# 03-MCU.net
KiCad netlist of a schematic drawn in Altium Designer
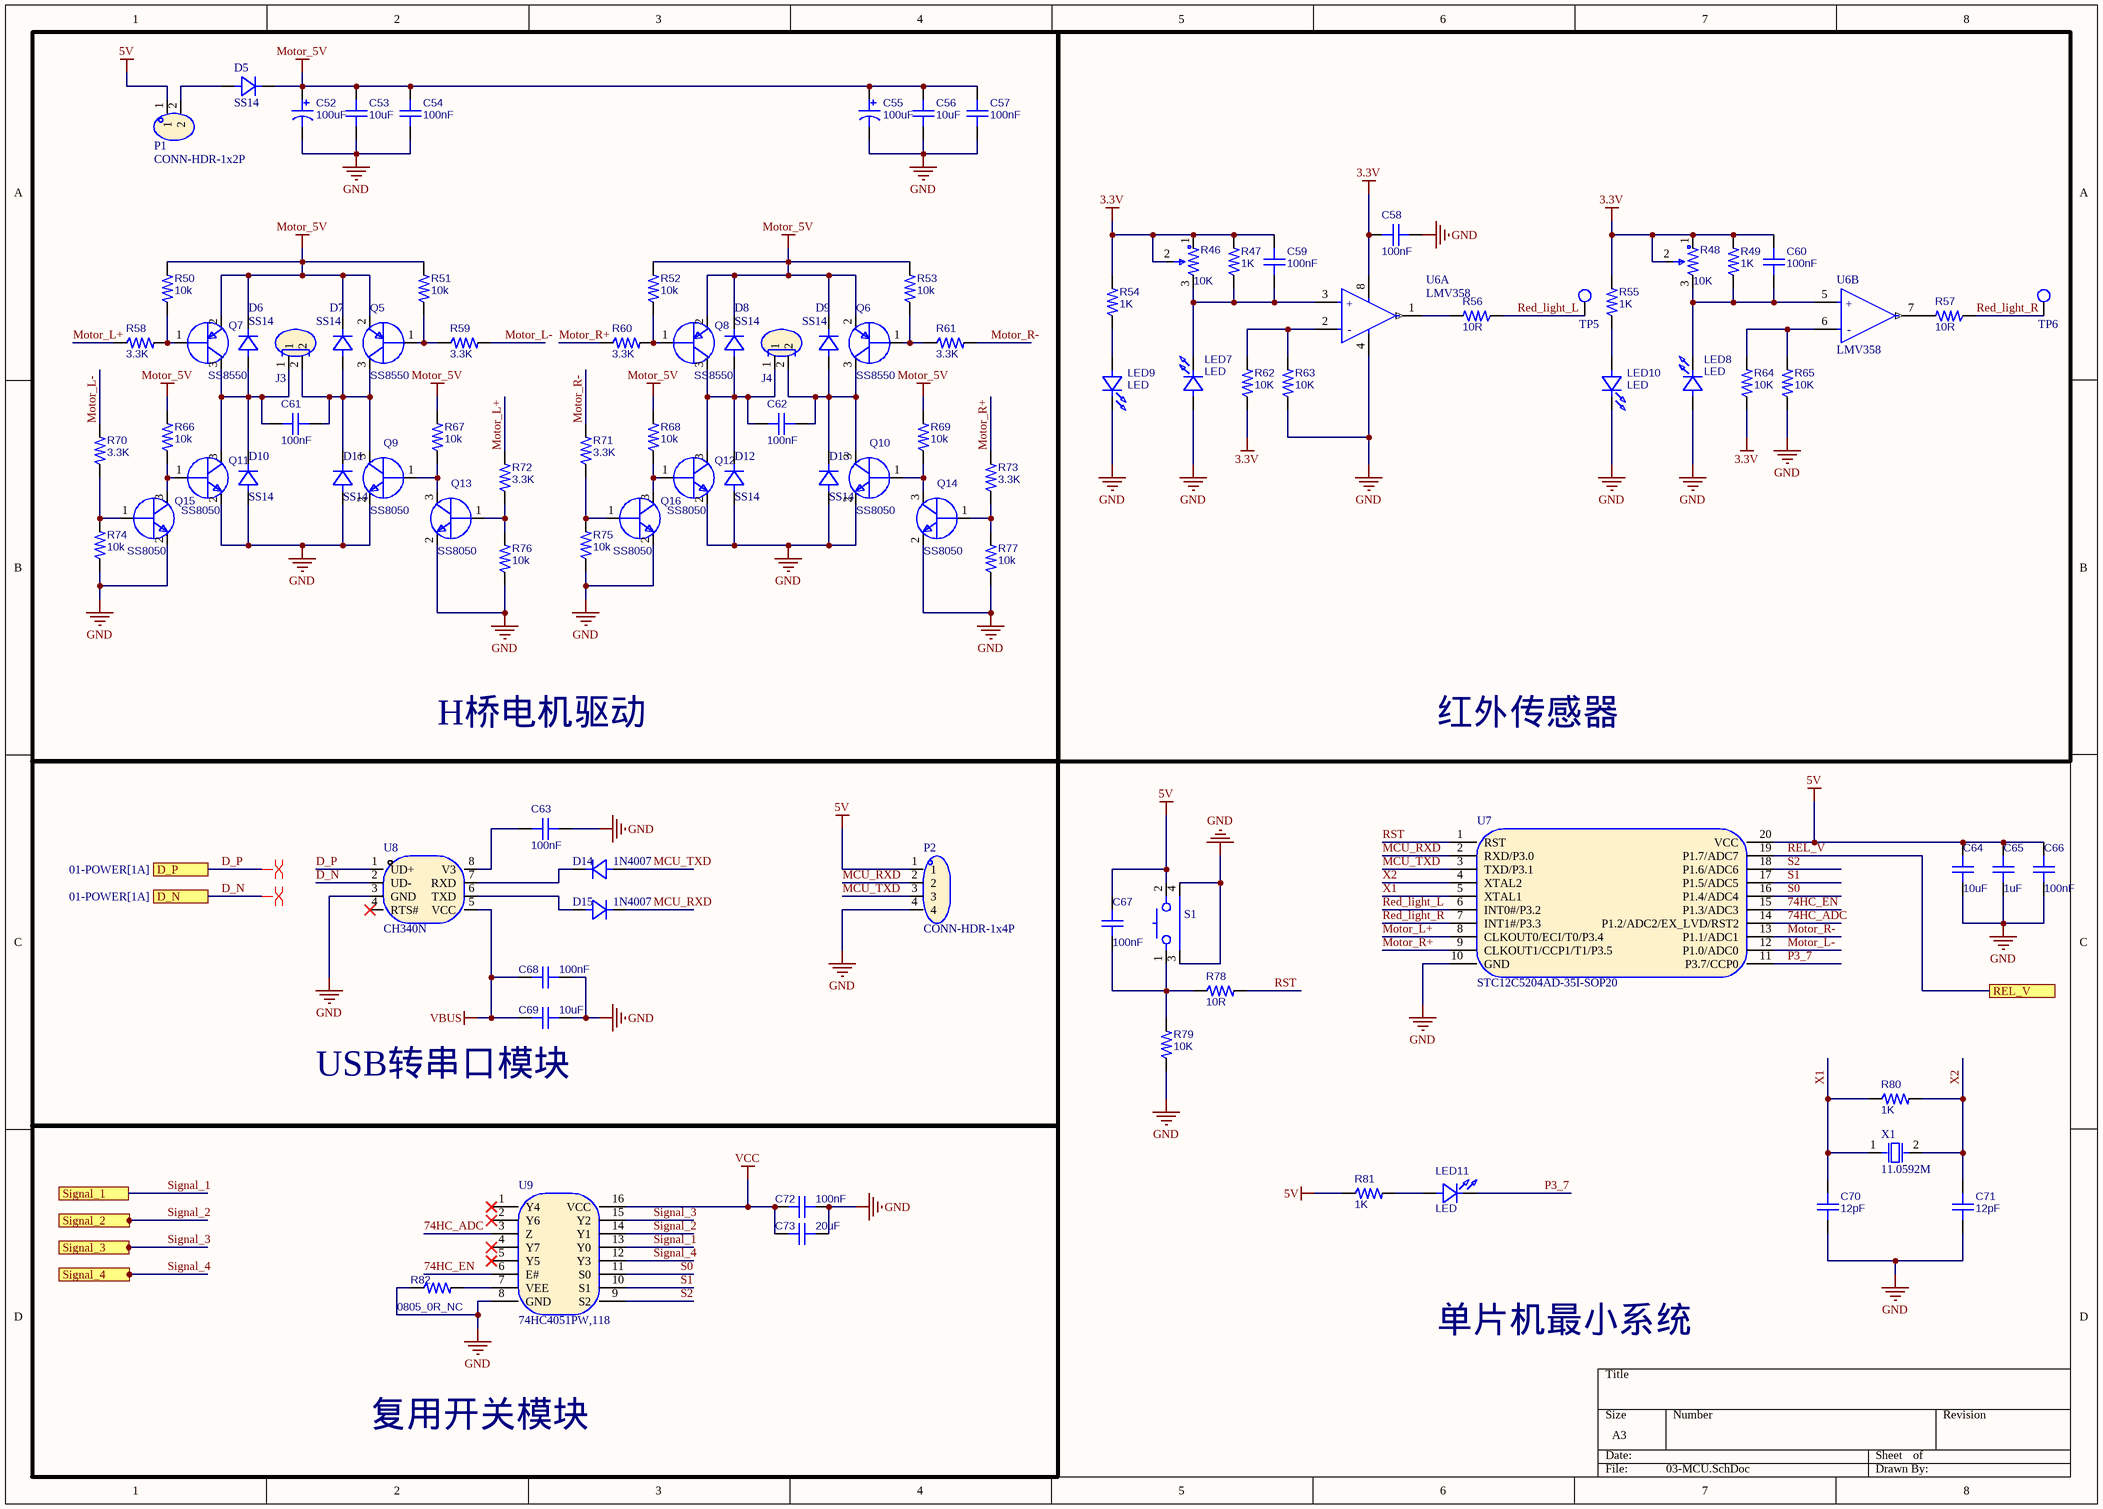
[diagram p0: 03-MCU.SchDoc]

(export (version "E")
  (design (tool "Eeschema 10.0.6"))
  (components
    (comp (ref "C52")
      (value "100uF")
      (footprint "CAPA-TH-5020-P2.0")
      (description "电解电容")
      (fields
        (field (name "BOM_MANUFACTURER PART") "普通黑色470UF 50V")
        (field (name "BOM_SUPPLIER PART") "C34642")
      )
      (libsource (lib "声源跟踪小车原理图库") (part "CAPA"))
    )
    (comp (ref "C53")
      (value "10uF")
      (footprint "CAP-SMD-0603")
      (description "贴片电容")
      (fields
        (field (name "BOM_MANUFACTURER PART") "CL03A104KQ3NNNC")
        (field (name "BOM_SUPPLIER PART") "C160831")
        (field (name "CONTRIBUTOR") "LCSC")
      )
      (libsource (lib "声源跟踪小车原理图库") (part "CAP"))
    )
    (comp (ref "C54")
      (value "100nF")
      (footprint "CAP-SMD-0603")
      (description "贴片电容")
      (fields
        (field (name "BOM_MANUFACTURER PART") "CL03A104KQ3NNNC")
        (field (name "BOM_SUPPLIER PART") "C160831")
        (field (name "CONTRIBUTOR") "LCSC")
      )
      (libsource (lib "声源跟踪小车原理图库") (part "CAP"))
    )
    (comp (ref "C55")
      (value "100uF")
      (footprint "CAPA-TH-5020-P2.0")
      (description "电解电容")
      (fields
        (field (name "BOM_MANUFACTURER PART") "普通黑色470UF 50V")
        (field (name "BOM_SUPPLIER PART") "C34642")
      )
      (libsource (lib "声源跟踪小车原理图库") (part "CAPA"))
    )
    (comp (ref "C56")
      (value "10uF")
      (footprint "CAP-SMD-0603")
      (description "贴片电容")
      (fields
        (field (name "BOM_MANUFACTURER PART") "CL03A104KQ3NNNC")
        (field (name "BOM_SUPPLIER PART") "C160831")
        (field (name "CONTRIBUTOR") "LCSC")
      )
      (libsource (lib "声源跟踪小车原理图库") (part "CAP"))
    )
    (comp (ref "C57")
      (value "100nF")
      (footprint "CAP-SMD-0603")
      (description "贴片电容")
      (fields
        (field (name "BOM_MANUFACTURER PART") "CL03A104KQ3NNNC")
        (field (name "BOM_SUPPLIER PART") "C160831")
        (field (name "CONTRIBUTOR") "LCSC")
      )
      (libsource (lib "声源跟踪小车原理图库") (part "CAP"))
    )
    (comp (ref "C58")
      (value "100nF")
      (footprint "CAP-SMD-0603")
      (description "贴片电容")
      (fields
        (field (name "BOM_MANUFACTURER PART") "CL03A104KQ3NNNC")
        (field (name "BOM_SUPPLIER PART") "C160831")
        (field (name "CONTRIBUTOR") "LCSC")
      )
      (libsource (lib "声源跟踪小车原理图库") (part "CAP"))
    )
    (comp (ref "C59")
      (value "100nF")
      (footprint "CAP-SMD-0603")
      (description "贴片电容")
      (fields
        (field (name "BOM_MANUFACTURER PART") "CL03A104KQ3NNNC")
        (field (name "BOM_SUPPLIER PART") "C160831")
        (field (name "CONTRIBUTOR") "LCSC")
      )
      (libsource (lib "声源跟踪小车原理图库") (part "CAP"))
    )
    (comp (ref "C60")
      (value "100nF")
      (footprint "CAP-SMD-0603")
      (description "贴片电容")
      (fields
        (field (name "BOM_MANUFACTURER PART") "CL03A104KQ3NNNC")
        (field (name "BOM_SUPPLIER PART") "C160831")
        (field (name "CONTRIBUTOR") "LCSC")
      )
      (libsource (lib "声源跟踪小车原理图库") (part "CAP"))
    )
    (comp (ref "C61")
      (value "100nF")
      (footprint "CAP-SMD-0603")
      (description "贴片电容")
      (fields
        (field (name "BOM_MANUFACTURER PART") "CL03A104KQ3NNNC")
        (field (name "BOM_SUPPLIER PART") "C160831")
        (field (name "CONTRIBUTOR") "LCSC")
      )
      (libsource (lib "声源跟踪小车原理图库") (part "CAP"))
    )
    (comp (ref "C62")
      (value "100nF")
      (footprint "CAP-SMD-0603")
      (description "贴片电容")
      (fields
        (field (name "BOM_MANUFACTURER PART") "CL03A104KQ3NNNC")
        (field (name "BOM_SUPPLIER PART") "C160831")
        (field (name "CONTRIBUTOR") "LCSC")
      )
      (libsource (lib "声源跟踪小车原理图库") (part "CAP"))
    )
    (comp (ref "C63")
      (value "100nF")
      (footprint "CAP-SMD-0603")
      (description "贴片电容")
      (fields
        (field (name "BOM_MANUFACTURER PART") "CL03A104KQ3NNNC")
        (field (name "BOM_SUPPLIER PART") "C160831")
        (field (name "CONTRIBUTOR") "LCSC")
      )
      (libsource (lib "声源跟踪小车原理图库") (part "CAP"))
    )
    (comp (ref "C64")
      (value "10uF")
      (footprint "CAP-SMD-0603")
      (description "贴片电容")
      (fields
        (field (name "BOM_MANUFACTURER PART") "CL03A104KQ3NNNC")
        (field (name "BOM_SUPPLIER PART") "C160831")
        (field (name "CONTRIBUTOR") "LCSC")
      )
      (libsource (lib "声源跟踪小车原理图库") (part "CAP"))
    )
    (comp (ref "C65")
      (value "1uF")
      (footprint "CAP-SMD-0603")
      (description "贴片电容")
      (fields
        (field (name "BOM_MANUFACTURER PART") "CL03A104KQ3NNNC")
        (field (name "BOM_SUPPLIER PART") "C160831")
        (field (name "CONTRIBUTOR") "LCSC")
      )
      (libsource (lib "声源跟踪小车原理图库") (part "CAP"))
    )
    (comp (ref "C66")
      (value "100nF")
      (footprint "CAP-SMD-0603")
      (description "贴片电容")
      (fields
        (field (name "BOM_MANUFACTURER PART") "CL03A104KQ3NNNC")
        (field (name "BOM_SUPPLIER PART") "C160831")
        (field (name "CONTRIBUTOR") "LCSC")
      )
      (libsource (lib "声源跟踪小车原理图库") (part "CAP"))
    )
    (comp (ref "C67")
      (value "100nF")
      (footprint "CAP-SMD-0603")
      (description "贴片电容")
      (fields
        (field (name "BOM_MANUFACTURER PART") "CL03A104KQ3NNNC")
        (field (name "BOM_SUPPLIER PART") "C160831")
        (field (name "CONTRIBUTOR") "LCSC")
      )
      (libsource (lib "声源跟踪小车原理图库") (part "CAP"))
    )
    (comp (ref "C68")
      (value "100nF")
      (footprint "CAP-SMD-0603")
      (description "贴片电容")
      (fields
        (field (name "BOM_MANUFACTURER PART") "CL03A104KQ3NNNC")
        (field (name "BOM_SUPPLIER PART") "C160831")
        (field (name "CONTRIBUTOR") "LCSC")
      )
      (libsource (lib "声源跟踪小车原理图库") (part "CAP"))
    )
    (comp (ref "C69")
      (value "10uF")
      (footprint "CAP-SMD-0603")
      (description "贴片电容")
      (fields
        (field (name "BOM_MANUFACTURER PART") "CL03A104KQ3NNNC")
        (field (name "BOM_SUPPLIER PART") "C160831")
        (field (name "CONTRIBUTOR") "LCSC")
      )
      (libsource (lib "声源跟踪小车原理图库") (part "CAP"))
    )
    (comp (ref "C70")
      (value "12pF")
      (footprint "CAP-SMD-0603")
      (description "贴片电容")
      (fields
        (field (name "BOM_MANUFACTURER PART") "CL03A104KQ3NNNC")
        (field (name "BOM_SUPPLIER PART") "C160831")
        (field (name "CONTRIBUTOR") "LCSC")
      )
      (libsource (lib "声源跟踪小车原理图库") (part "CAP"))
    )
    (comp (ref "C71")
      (value "12pF")
      (footprint "CAP-SMD-0603")
      (description "贴片电容")
      (fields
        (field (name "BOM_MANUFACTURER PART") "CL03A104KQ3NNNC")
        (field (name "BOM_SUPPLIER PART") "C160831")
        (field (name "CONTRIBUTOR") "LCSC")
      )
      (libsource (lib "声源跟踪小车原理图库") (part "CAP"))
    )
    (comp (ref "C72")
      (value "100nF")
      (footprint "CAP-SMD-0603")
      (description "贴片电容")
      (fields
        (field (name "BOM_MANUFACTURER PART") "CL03A104KQ3NNNC")
        (field (name "BOM_SUPPLIER PART") "C160831")
        (field (name "CONTRIBUTOR") "LCSC")
      )
      (libsource (lib "声源跟踪小车原理图库") (part "CAP"))
    )
    (comp (ref "C73")
      (value "20uF")
      (footprint "CAP-SMD-0603")
      (description "贴片电容")
      (fields
        (field (name "BOM_MANUFACTURER PART") "CL03A104KQ3NNNC")
        (field (name "BOM_SUPPLIER PART") "C160831")
        (field (name "CONTRIBUTOR") "LCSC")
      )
      (libsource (lib "声源跟踪小车原理图库") (part "CAP"))
    )
    (comp (ref "D5")
      (value "SS14")
      (footprint "SOD-123-P3.4")
      (description "二极管1N4148W")
      (fields (field (name "MANUFACTURER") "PSI(宝力芯)") (field (name "MANUFACTURER PART") "1N4148W"))
      (libsource (lib "声源跟踪小车原理图库") (part "Diode"))
    )
    (comp (ref "D6")
      (value "SS14")
      (footprint "SOD-123-P3.4")
      (description "二极管1N4148W")
      (fields (field (name "MANUFACTURER") "PSI(宝力芯)") (field (name "MANUFACTURER PART") "1N4148W"))
      (libsource (lib "声源跟踪小车原理图库") (part "Diode"))
    )
    (comp (ref "D7")
      (value "SS14")
      (footprint "SOD-123-P3.4")
      (description "二极管1N4148W")
      (fields (field (name "MANUFACTURER") "PSI(宝力芯)") (field (name "MANUFACTURER PART") "1N4148W"))
      (libsource (lib "声源跟踪小车原理图库") (part "Diode"))
    )
    (comp (ref "D8")
      (value "SS14")
      (footprint "SOD-123-P3.4")
      (description "二极管1N4148W")
      (fields (field (name "MANUFACTURER") "PSI(宝力芯)") (field (name "MANUFACTURER PART") "1N4148W"))
      (libsource (lib "声源跟踪小车原理图库") (part "Diode"))
    )
    (comp (ref "D9")
      (value "SS14")
      (footprint "SOD-123-P3.4")
      (description "二极管1N4148W")
      (fields (field (name "MANUFACTURER") "PSI(宝力芯)") (field (name "MANUFACTURER PART") "1N4148W"))
      (libsource (lib "声源跟踪小车原理图库") (part "Diode"))
    )
    (comp (ref "D10")
      (value "SS14")
      (footprint "SOD-123-P3.4")
      (description "二极管1N4148W")
      (fields (field (name "MANUFACTURER") "PSI(宝力芯)") (field (name "MANUFACTURER PART") "1N4148W"))
      (libsource (lib "声源跟踪小车原理图库") (part "Diode"))
    )
    (comp (ref "D11")
      (value "SS14")
      (footprint "SOD-123-P3.4")
      (description "二极管1N4148W")
      (fields (field (name "MANUFACTURER") "PSI(宝力芯)") (field (name "MANUFACTURER PART") "1N4148W"))
      (libsource (lib "声源跟踪小车原理图库") (part "Diode"))
    )
    (comp (ref "D12")
      (value "SS14")
      (footprint "SOD-123-P3.4")
      (description "二极管1N4148W")
      (fields (field (name "MANUFACTURER") "PSI(宝力芯)") (field (name "MANUFACTURER PART") "1N4148W"))
      (libsource (lib "声源跟踪小车原理图库") (part "Diode"))
    )
    (comp (ref "D13")
      (value "SS14")
      (footprint "SOD-123-P3.4")
      (description "二极管1N4148W")
      (fields (field (name "MANUFACTURER") "PSI(宝力芯)") (field (name "MANUFACTURER PART") "1N4148W"))
      (libsource (lib "声源跟踪小车原理图库") (part "Diode"))
    )
    (comp (ref "D14")
      (value "1N4007")
      (footprint "SOD-123-P3.4")
      (description "二极管1N4148W")
      (fields (field (name "MANUFACTURER") "PSI(宝力芯)") (field (name "MANUFACTURER PART") "1N4148W"))
      (libsource (lib "声源跟踪小车原理图库") (part "Diode"))
    )
    (comp (ref "D15")
      (value "1N4007")
      (footprint "SOD-123-P3.4")
      (description "二极管1N4148W")
      (fields (field (name "MANUFACTURER") "PSI(宝力芯)") (field (name "MANUFACTURER PART") "1N4148W"))
      (libsource (lib "声源跟踪小车原理图库") (part "Diode"))
    )
    (comp (ref "J3")
      (value "CONN-2P")
      (footprint "CONN-TH-CDS-1x2P-P2.54")
      (description "连接插座2pin")
      (fields (field (name "MANUFACTURER") "KEFA(科发)") (field (name "MANUFACTURER PART") "KF301-5.0-2P"))
      (libsource (lib "声源跟踪小车原理图库") (part "CONN-2P"))
    )
    (comp (ref "J4")
      (value "CONN-2P")
      (footprint "CONN-TH-CDS-1x2P-P2.54")
      (description "连接插座2pin")
      (fields (field (name "MANUFACTURER") "KEFA(科发)") (field (name "MANUFACTURER PART") "KF301-5.0-2P"))
      (libsource (lib "声源跟踪小车原理图库") (part "CONN-2P"))
    )
    (comp (ref "LED7")
      (value "LED")
      (footprint "LED-SMD-0805")
      (description "LED灯,发光二极管")
      (fields
        (field (name "BOM_SUPPLIER PART") "C434447")
        (field (name "BOM_MANUFACTURER PART") "SZYY0402B")
        (field (name "CONTRIBUTOR") "LCSC")
      )
      (libsource (lib "声源跟踪小车原理图库") (part "LED"))
    )
    (comp (ref "LED8")
      (value "LED")
      (footprint "LED-SMD-0805")
      (description "LED灯,发光二极管")
      (fields
        (field (name "BOM_SUPPLIER PART") "C434447")
        (field (name "BOM_MANUFACTURER PART") "SZYY0402B")
        (field (name "CONTRIBUTOR") "LCSC")
      )
      (libsource (lib "声源跟踪小车原理图库") (part "LED"))
    )
    (comp (ref "LED9")
      (value "LED")
      (footprint "LED-SMD-0805")
      (description "LED灯,发光二极管")
      (fields
        (field (name "BOM_SUPPLIER PART") "C434447")
        (field (name "BOM_MANUFACTURER PART") "SZYY0402B")
        (field (name "CONTRIBUTOR") "LCSC")
      )
      (libsource (lib "声源跟踪小车原理图库") (part "LED"))
    )
    (comp (ref "LED10")
      (value "LED")
      (footprint "LED-SMD-0805")
      (description "LED灯,发光二极管")
      (fields
        (field (name "BOM_SUPPLIER PART") "C434447")
        (field (name "BOM_MANUFACTURER PART") "SZYY0402B")
        (field (name "CONTRIBUTOR") "LCSC")
      )
      (libsource (lib "声源跟踪小车原理图库") (part "LED"))
    )
    (comp (ref "LED11")
      (value "LED")
      (footprint "LED-SMD-0805")
      (description "LED灯,发光二极管")
      (fields
        (field (name "BOM_SUPPLIER PART") "C434447")
        (field (name "BOM_MANUFACTURER PART") "SZYY0402B")
        (field (name "CONTRIBUTOR") "LCSC")
      )
      (libsource (lib "声源跟踪小车原理图库") (part "LED"))
    )
    (comp (ref "P1")
      (value "CONN-HDR-1x2P")
      (footprint "CONN-TH-1X2P-P2.54")
      (description "排针1*2pin")
      (fields
        (field (name "MANUFACTURER") "kinghelm(金航标)")
        (field (name "MANUFACTURER PART") "KH-2.54PH180-1X2P-L11.5")
      )
      (libsource (lib "声源跟踪小车原理图库") (part "CONN-HDR-1x2P"))
    )
    (comp (ref "P2")
      (value "CONN-HDR-1x4P")
      (footprint "CONN-TH-1X4P-P2.54")
      (description "排针1*4pin")
      (fields
        (field (name "MANUFACTURER") "Wcon(维峰电子)")
        (field (name "MANUFACTURER PART") "1125-1104G0S116C001")
      )
      (libsource (lib "声源跟踪小车原理图库") (part "CONN-HDR-1x4P"))
    )
    (comp (ref "Q5")
      (value "SS8550")
      (footprint "SOT-23-3-LP2.28-P1.91")
      (description "贴片PNP三极管")
      (fields
        (field (name "BOM_SUPPLIER PART") "C2891799")
        (field (name "BOM_MANUFACTURER PART") "S9012")
        (field (name "CONTRIBUTOR") "LCSC")
      )
      (libsource (lib "声源跟踪小车原理图库") (part "PNP-SOT-23-3"))
    )
    (comp (ref "Q6")
      (value "SS8550")
      (footprint "SOT-23-3-LP2.28-P1.91")
      (description "贴片PNP三极管")
      (fields
        (field (name "BOM_SUPPLIER PART") "C2891799")
        (field (name "BOM_MANUFACTURER PART") "S9012")
        (field (name "CONTRIBUTOR") "LCSC")
      )
      (libsource (lib "声源跟踪小车原理图库") (part "PNP-SOT-23-3"))
    )
    (comp (ref "Q7")
      (value "SS8550")
      (footprint "SOT-23-3-LP2.28-P1.91")
      (description "贴片PNP三极管")
      (fields
        (field (name "BOM_SUPPLIER PART") "C2891799")
        (field (name "BOM_MANUFACTURER PART") "S9012")
        (field (name "CONTRIBUTOR") "LCSC")
      )
      (libsource (lib "声源跟踪小车原理图库") (part "PNP-SOT-23-3"))
    )
    (comp (ref "Q8")
      (value "SS8550")
      (footprint "SOT-23-3-LP2.28-P1.91")
      (description "贴片PNP三极管")
      (fields
        (field (name "BOM_SUPPLIER PART") "C2891799")
        (field (name "BOM_MANUFACTURER PART") "S9012")
        (field (name "CONTRIBUTOR") "LCSC")
      )
      (libsource (lib "声源跟踪小车原理图库") (part "PNP-SOT-23-3"))
    )
    (comp (ref "Q9")
      (value "SS8050")
      (footprint "SOT-23-3-LP2.28-P1.91")
      (description "贴片NPN三极管")
      (fields
        (field (name "BOM_SUPPLIER PART") "C2898668")
        (field (name "BOM_MANUFACTURER PART") "S9013")
        (field (name "CONTRIBUTOR") "LCSC")
      )
      (libsource (lib "声源跟踪小车原理图库") (part "NPN-SOT-23-3"))
    )
    (comp (ref "Q10")
      (value "SS8050")
      (footprint "SOT-23-3-LP2.28-P1.91")
      (description "贴片NPN三极管")
      (fields
        (field (name "BOM_SUPPLIER PART") "C2898668")
        (field (name "BOM_MANUFACTURER PART") "S9013")
        (field (name "CONTRIBUTOR") "LCSC")
      )
      (libsource (lib "声源跟踪小车原理图库") (part "NPN-SOT-23-3"))
    )
    (comp (ref "Q11")
      (value "SS8050")
      (footprint "SOT-23-3-LP2.28-P1.91")
      (description "贴片NPN三极管")
      (fields
        (field (name "BOM_SUPPLIER PART") "C2898668")
        (field (name "BOM_MANUFACTURER PART") "S9013")
        (field (name "CONTRIBUTOR") "LCSC")
      )
      (libsource (lib "声源跟踪小车原理图库") (part "NPN-SOT-23-3"))
    )
    (comp (ref "Q12")
      (value "SS8050")
      (footprint "SOT-23-3-LP2.28-P1.91")
      (description "贴片NPN三极管")
      (fields
        (field (name "BOM_SUPPLIER PART") "C2898668")
        (field (name "BOM_MANUFACTURER PART") "S9013")
        (field (name "CONTRIBUTOR") "LCSC")
      )
      (libsource (lib "声源跟踪小车原理图库") (part "NPN-SOT-23-3"))
    )
    (comp (ref "Q13")
      (value "SS8050")
      (footprint "SOT-23-3-LP2.28-P1.91")
      (description "贴片NPN三极管")
      (fields
        (field (name "BOM_SUPPLIER PART") "C2898668")
        (field (name "BOM_MANUFACTURER PART") "S9013")
        (field (name "CONTRIBUTOR") "LCSC")
      )
      (libsource (lib "声源跟踪小车原理图库") (part "NPN-SOT-23-3"))
    )
    (comp (ref "Q14")
      (value "SS8050")
      (footprint "SOT-23-3-LP2.28-P1.91")
      (description "贴片NPN三极管")
      (fields
        (field (name "BOM_SUPPLIER PART") "C2898668")
        (field (name "BOM_MANUFACTURER PART") "S9013")
        (field (name "CONTRIBUTOR") "LCSC")
      )
      (libsource (lib "声源跟踪小车原理图库") (part "NPN-SOT-23-3"))
    )
    (comp (ref "Q15")
      (value "SS8050")
      (footprint "SOT-23-3-LP2.28-P1.91")
      (description "贴片NPN三极管")
      (fields
        (field (name "BOM_SUPPLIER PART") "C2898668")
        (field (name "BOM_MANUFACTURER PART") "S9013")
        (field (name "CONTRIBUTOR") "LCSC")
      )
      (libsource (lib "声源跟踪小车原理图库") (part "NPN-SOT-23-3"))
    )
    (comp (ref "Q16")
      (value "SS8050")
      (footprint "SOT-23-3-LP2.28-P1.91")
      (description "贴片NPN三极管")
      (fields
        (field (name "BOM_SUPPLIER PART") "C2898668")
        (field (name "BOM_MANUFACTURER PART") "S9013")
        (field (name "CONTRIBUTOR") "LCSC")
      )
      (libsource (lib "声源跟踪小车原理图库") (part "NPN-SOT-23-3"))
    )
    (comp (ref "R46")
      (value "10K")
      (footprint "RES-SMD-ADJ-3224W")
      (description "可调电阻,电位器")
      (fields
        (field (name "BOM_SUPPLIER PART") "C118966")
        (field (name "BOM_MANUFACTURER PART") "3362P-1-104")
        (field (name "CONTRIBUTOR") "LCSC")
      )
      (libsource (lib "声源跟踪小车原理图库") (part "RES-ADJ"))
    )
    (comp (ref "R47")
      (value "1K")
      (footprint "RES-SMD-0603")
      (description "贴片电阻")
      (fields
        (field (name "BOM_SUPPLIER PART") "C118966")
        (field (name "BOM_MANUFACTURER PART") "3362P-1-104")
        (field (name "CONTRIBUTOR") "LCSC")
      )
      (libsource (lib "声源跟踪小车原理图库") (part "RES"))
    )
    (comp (ref "R48")
      (value "10K")
      (footprint "RES-SMD-ADJ-3224W")
      (description "可调电阻,电位器")
      (fields
        (field (name "BOM_SUPPLIER PART") "C118966")
        (field (name "BOM_MANUFACTURER PART") "3362P-1-104")
        (field (name "CONTRIBUTOR") "LCSC")
      )
      (libsource (lib "声源跟踪小车原理图库") (part "RES-ADJ"))
    )
    (comp (ref "R49")
      (value "1K")
      (footprint "RES-SMD-0603")
      (description "贴片电阻")
      (fields
        (field (name "BOM_SUPPLIER PART") "C118966")
        (field (name "BOM_MANUFACTURER PART") "3362P-1-104")
        (field (name "CONTRIBUTOR") "LCSC")
      )
      (libsource (lib "声源跟踪小车原理图库") (part "RES"))
    )
    (comp (ref "R50")
      (value "10k")
      (footprint "RES-SMD-0603")
      (description "贴片电阻")
      (fields
        (field (name "BOM_SUPPLIER PART") "C118966")
        (field (name "BOM_MANUFACTURER PART") "3362P-1-104")
        (field (name "CONTRIBUTOR") "LCSC")
      )
      (libsource (lib "声源跟踪小车原理图库") (part "RES"))
    )
    (comp (ref "R51")
      (value "10k")
      (footprint "RES-SMD-0603")
      (description "贴片电阻")
      (fields
        (field (name "BOM_SUPPLIER PART") "C118966")
        (field (name "BOM_MANUFACTURER PART") "3362P-1-104")
        (field (name "CONTRIBUTOR") "LCSC")
      )
      (libsource (lib "声源跟踪小车原理图库") (part "RES"))
    )
    (comp (ref "R52")
      (value "10k")
      (footprint "RES-SMD-0603")
      (description "贴片电阻")
      (fields
        (field (name "BOM_SUPPLIER PART") "C118966")
        (field (name "BOM_MANUFACTURER PART") "3362P-1-104")
        (field (name "CONTRIBUTOR") "LCSC")
      )
      (libsource (lib "声源跟踪小车原理图库") (part "RES"))
    )
    (comp (ref "R53")
      (value "10k")
      (footprint "RES-SMD-0603")
      (description "贴片电阻")
      (fields
        (field (name "BOM_SUPPLIER PART") "C118966")
        (field (name "BOM_MANUFACTURER PART") "3362P-1-104")
        (field (name "CONTRIBUTOR") "LCSC")
      )
      (libsource (lib "声源跟踪小车原理图库") (part "RES"))
    )
    (comp (ref "R54")
      (value "1K")
      (footprint "RES-SMD-0603")
      (description "贴片电阻")
      (fields
        (field (name "BOM_SUPPLIER PART") "C118966")
        (field (name "BOM_MANUFACTURER PART") "3362P-1-104")
        (field (name "CONTRIBUTOR") "LCSC")
      )
      (libsource (lib "声源跟踪小车原理图库") (part "RES"))
    )
    (comp (ref "R55")
      (value "1K")
      (footprint "RES-SMD-0603")
      (description "贴片电阻")
      (fields
        (field (name "BOM_SUPPLIER PART") "C118966")
        (field (name "BOM_MANUFACTURER PART") "3362P-1-104")
        (field (name "CONTRIBUTOR") "LCSC")
      )
      (libsource (lib "声源跟踪小车原理图库") (part "RES"))
    )
    (comp (ref "R56")
      (value "10R")
      (footprint "RES-SMD-0603")
      (description "贴片电阻")
      (fields
        (field (name "BOM_SUPPLIER PART") "C118966")
        (field (name "BOM_MANUFACTURER PART") "3362P-1-104")
        (field (name "CONTRIBUTOR") "LCSC")
      )
      (libsource (lib "声源跟踪小车原理图库") (part "RES"))
    )
    (comp (ref "R57")
      (value "10R")
      (footprint "RES-SMD-0603")
      (description "贴片电阻")
      (fields
        (field (name "BOM_SUPPLIER PART") "C118966")
        (field (name "BOM_MANUFACTURER PART") "3362P-1-104")
        (field (name "CONTRIBUTOR") "LCSC")
      )
      (libsource (lib "声源跟踪小车原理图库") (part "RES"))
    )
    (comp (ref "R58")
      (value "3.3K")
      (footprint "RES-SMD-0603")
      (description "贴片电阻")
      (fields
        (field (name "BOM_SUPPLIER PART") "C118966")
        (field (name "BOM_MANUFACTURER PART") "3362P-1-104")
        (field (name "CONTRIBUTOR") "LCSC")
      )
      (libsource (lib "声源跟踪小车原理图库") (part "RES"))
    )
    (comp (ref "R59")
      (value "3.3K")
      (footprint "RES-SMD-0603")
      (description "贴片电阻")
      (fields
        (field (name "BOM_SUPPLIER PART") "C118966")
        (field (name "BOM_MANUFACTURER PART") "3362P-1-104")
        (field (name "CONTRIBUTOR") "LCSC")
      )
      (libsource (lib "声源跟踪小车原理图库") (part "RES"))
    )
    (comp (ref "R60")
      (value "3.3K")
      (footprint "RES-SMD-0603")
      (description "贴片电阻")
      (fields
        (field (name "BOM_SUPPLIER PART") "C118966")
        (field (name "BOM_MANUFACTURER PART") "3362P-1-104")
        (field (name "CONTRIBUTOR") "LCSC")
      )
      (libsource (lib "声源跟踪小车原理图库") (part "RES"))
    )
    (comp (ref "R61")
      (value "3.3K")
      (footprint "RES-SMD-0603")
      (description "贴片电阻")
      (fields
        (field (name "BOM_SUPPLIER PART") "C118966")
        (field (name "BOM_MANUFACTURER PART") "3362P-1-104")
        (field (name "CONTRIBUTOR") "LCSC")
      )
      (libsource (lib "声源跟踪小车原理图库") (part "RES"))
    )
    (comp (ref "R62")
      (value "10K")
      (footprint "RES-SMD-0603")
      (description "贴片电阻")
      (fields
        (field (name "BOM_SUPPLIER PART") "C118966")
        (field (name "BOM_MANUFACTURER PART") "3362P-1-104")
        (field (name "CONTRIBUTOR") "LCSC")
      )
      (libsource (lib "声源跟踪小车原理图库") (part "RES"))
    )
    (comp (ref "R63")
      (value "10K")
      (footprint "RES-SMD-0603")
      (description "贴片电阻")
      (fields
        (field (name "BOM_SUPPLIER PART") "C118966")
        (field (name "BOM_MANUFACTURER PART") "3362P-1-104")
        (field (name "CONTRIBUTOR") "LCSC")
      )
      (libsource (lib "声源跟踪小车原理图库") (part "RES"))
    )
    (comp (ref "R64")
      (value "10K")
      (footprint "RES-SMD-0603")
      (description "贴片电阻")
      (fields
        (field (name "BOM_SUPPLIER PART") "C118966")
        (field (name "BOM_MANUFACTURER PART") "3362P-1-104")
        (field (name "CONTRIBUTOR") "LCSC")
      )
      (libsource (lib "声源跟踪小车原理图库") (part "RES"))
    )
    (comp (ref "R65")
      (value "10K")
      (footprint "RES-SMD-0603")
      (description "贴片电阻")
      (fields
        (field (name "BOM_SUPPLIER PART") "C118966")
        (field (name "BOM_MANUFACTURER PART") "3362P-1-104")
        (field (name "CONTRIBUTOR") "LCSC")
      )
      (libsource (lib "声源跟踪小车原理图库") (part "RES"))
    )
    (comp (ref "R66")
      (value "10k")
      (footprint "RES-SMD-0603")
      (description "贴片电阻")
      (fields
        (field (name "BOM_SUPPLIER PART") "C118966")
        (field (name "BOM_MANUFACTURER PART") "3362P-1-104")
        (field (name "CONTRIBUTOR") "LCSC")
      )
      (libsource (lib "声源跟踪小车原理图库") (part "RES"))
    )
    (comp (ref "R67")
      (value "10k")
      (footprint "RES-SMD-0603")
      (description "贴片电阻")
      (fields
        (field (name "BOM_SUPPLIER PART") "C118966")
        (field (name "BOM_MANUFACTURER PART") "3362P-1-104")
        (field (name "CONTRIBUTOR") "LCSC")
      )
      (libsource (lib "声源跟踪小车原理图库") (part "RES"))
    )
    (comp (ref "R68")
      (value "10k")
      (footprint "RES-SMD-0603")
      (description "贴片电阻")
      (fields
        (field (name "BOM_SUPPLIER PART") "C118966")
        (field (name "BOM_MANUFACTURER PART") "3362P-1-104")
        (field (name "CONTRIBUTOR") "LCSC")
      )
      (libsource (lib "声源跟踪小车原理图库") (part "RES"))
    )
    (comp (ref "R69")
      (value "10k")
      (footprint "RES-SMD-0603")
      (description "贴片电阻")
      (fields
        (field (name "BOM_SUPPLIER PART") "C118966")
        (field (name "BOM_MANUFACTURER PART") "3362P-1-104")
        (field (name "CONTRIBUTOR") "LCSC")
      )
      (libsource (lib "声源跟踪小车原理图库") (part "RES"))
    )
    (comp (ref "R70")
      (value "3.3K")
      (footprint "RES-SMD-0603")
      (description "贴片电阻")
      (fields
        (field (name "BOM_SUPPLIER PART") "C118966")
        (field (name "BOM_MANUFACTURER PART") "3362P-1-104")
        (field (name "CONTRIBUTOR") "LCSC")
      )
      (libsource (lib "声源跟踪小车原理图库") (part "RES"))
    )
    (comp (ref "R71")
      (value "3.3K")
      (footprint "RES-SMD-0603")
      (description "贴片电阻")
      (fields
        (field (name "BOM_SUPPLIER PART") "C118966")
        (field (name "BOM_MANUFACTURER PART") "3362P-1-104")
        (field (name "CONTRIBUTOR") "LCSC")
      )
      (libsource (lib "声源跟踪小车原理图库") (part "RES"))
    )
    (comp (ref "R72")
      (value "3.3K")
      (footprint "RES-SMD-0603")
      (description "贴片电阻")
      (fields
        (field (name "BOM_SUPPLIER PART") "C118966")
        (field (name "BOM_MANUFACTURER PART") "3362P-1-104")
        (field (name "CONTRIBUTOR") "LCSC")
      )
      (libsource (lib "声源跟踪小车原理图库") (part "RES"))
    )
    (comp (ref "R73")
      (value "3.3K")
      (footprint "RES-SMD-0603")
      (description "贴片电阻")
      (fields
        (field (name "BOM_SUPPLIER PART") "C118966")
        (field (name "BOM_MANUFACTURER PART") "3362P-1-104")
        (field (name "CONTRIBUTOR") "LCSC")
      )
      (libsource (lib "声源跟踪小车原理图库") (part "RES"))
    )
    (comp (ref "R74")
      (value "10k")
      (footprint "RES-SMD-0603")
      (description "贴片电阻")
      (fields
        (field (name "BOM_SUPPLIER PART") "C118966")
        (field (name "BOM_MANUFACTURER PART") "3362P-1-104")
        (field (name "CONTRIBUTOR") "LCSC")
      )
      (libsource (lib "声源跟踪小车原理图库") (part "RES"))
    )
    (comp (ref "R75")
      (value "10k")
      (footprint "RES-SMD-0603")
      (description "贴片电阻")
      (fields
        (field (name "BOM_SUPPLIER PART") "C118966")
        (field (name "BOM_MANUFACTURER PART") "3362P-1-104")
        (field (name "CONTRIBUTOR") "LCSC")
      )
      (libsource (lib "声源跟踪小车原理图库") (part "RES"))
    )
    (comp (ref "R76")
      (value "10k")
      (footprint "RES-SMD-0603")
      (description "贴片电阻")
      (fields
        (field (name "BOM_SUPPLIER PART") "C118966")
        (field (name "BOM_MANUFACTURER PART") "3362P-1-104")
        (field (name "CONTRIBUTOR") "LCSC")
      )
      (libsource (lib "声源跟踪小车原理图库") (part "RES"))
    )
    (comp (ref "R77")
      (value "10k")
      (footprint "RES-SMD-0603")
      (description "贴片电阻")
      (fields
        (field (name "BOM_SUPPLIER PART") "C118966")
        (field (name "BOM_MANUFACTURER PART") "3362P-1-104")
        (field (name "CONTRIBUTOR") "LCSC")
      )
      (libsource (lib "声源跟踪小车原理图库") (part "RES"))
    )
    (comp (ref "R78")
      (value "10R")
      (footprint "RES-SMD-0603")
      (description "贴片电阻")
      (fields
        (field (name "BOM_SUPPLIER PART") "C118966")
        (field (name "BOM_MANUFACTURER PART") "3362P-1-104")
        (field (name "CONTRIBUTOR") "LCSC")
      )
      (libsource (lib "声源跟踪小车原理图库") (part "RES"))
    )
    (comp (ref "R79")
      (value "10K")
      (footprint "RES-SMD-0603")
      (description "贴片电阻")
      (fields
        (field (name "BOM_SUPPLIER PART") "C118966")
        (field (name "BOM_MANUFACTURER PART") "3362P-1-104")
        (field (name "CONTRIBUTOR") "LCSC")
      )
      (libsource (lib "声源跟踪小车原理图库") (part "RES"))
    )
    (comp (ref "R80")
      (value "1K")
      (footprint "RES-SMD-0603")
      (description "贴片电阻")
      (fields
        (field (name "BOM_SUPPLIER PART") "C118966")
        (field (name "BOM_MANUFACTURER PART") "3362P-1-104")
        (field (name "CONTRIBUTOR") "LCSC")
      )
      (libsource (lib "声源跟踪小车原理图库") (part "RES"))
    )
    (comp (ref "R81")
      (value "1K")
      (footprint "RES-SMD-0603")
      (description "贴片电阻")
      (fields
        (field (name "BOM_SUPPLIER PART") "C118966")
        (field (name "BOM_MANUFACTURER PART") "3362P-1-104")
        (field (name "CONTRIBUTOR") "LCSC")
      )
      (libsource (lib "声源跟踪小车原理图库") (part "RES"))
    )
    (comp (ref "R82")
      (value "0805_0R_NC")
      (footprint "RES-SMD-0603")
      (description "贴片电阻")
      (fields
        (field (name "BOM_SUPPLIER PART") "C118966")
        (field (name "BOM_MANUFACTURER PART") "3362P-1-104")
        (field (name "CONTRIBUTOR") "LCSC")
      )
      (libsource (lib "声源跟踪小车原理图库") (part "RES"))
    )
    (comp (ref "S1")
      (value "KEY-B-2P")
      (footprint "KEY-TH-B-2P")
      (description "按键开关B")
      (fields (field (name "MANUFACTURER") "C&K") (field (name "MANUFACTURER PART") "PTS645VL83LFS"))
      (libsource (lib "声源跟踪小车原理图库") (part "KEY-B-2P"))
    )
    (comp (ref "TP5")
      (value "TP")
      (footprint "TP")
      (description "TP测试点")
      (libsource (lib "声源跟踪小车原理图库") (part "TP"))
    )
    (comp (ref "TP6")
      (value "TP")
      (footprint "TP")
      (description "TP测试点")
      (libsource (lib "声源跟踪小车原理图库") (part "TP"))
    )
    (comp (ref "U6")
      (value "LMV358")
      (footprint "SOIC-8-LP5.5-P1.27")
      (description "运放IC OPAMP GP 2 CIRCUIT 8SOIC")
      (libsource (lib "声源跟踪小车原理图库") (part "LMV358"))
    )
    (comp (ref "U7")
      (value "STC12C5204AD-35I-SOP20")
      (footprint "SOIC-20-LP9.5-P1.27")
      (fields (field (name "MANUFACTURER") "STC(宏晶)"))
      (libsource (lib "声源跟踪小车原理图库") (part "STC12C5204AD-35I-SOP20"))
    )
    (comp (ref "U8")
      (value "CH340N")
      (footprint "SOP-8-LP5.3-P1.27")
      (fields (field (name "MANUFACTURER") "WCH(南京沁恒)"))
      (libsource (lib "声源跟踪小车原理图库") (part "CH340N"))
    )
    (comp (ref "U9")
      (value "74HC4051PW,118")
      (footprint "TSSOP-16-LP5.7-P0.65")
      (description "复用开关IC MUX/DEMUX 8X1")
      (fields (field (name "MANUFACTURER") "Nexperia(安世)"))
      (libsource (lib "声源跟踪小车原理图库") (part "74HC4051PW,118"))
    )
    (comp (ref "X1")
      (value "11.0592M")
      (footprint "OSC-5032-SMD-2P")
      (description "无源晶振2pin")
      (fields (field (name "MANUFACTURER") "YXC扬兴科技") (field (name "MANUFACTURER PART") "X49SM16MSD2SI"))
      (libsource (lib "声源跟踪小车原理图库") (part "XTAL-2P-WY"))
    )
  )
  (nets
    (net (code "1") (name "/74HC_ADC") (class "Default")
      (node (ref "U7") (pin "14") (pinfunction "P1.2/ADC2/EX_LVD/RST2_14") (pintype "passive"))
      (node (ref "U9") (pin "3") (pinfunction "Z_3") (pintype "passive"))
    )
    (net (code "2") (name "/74HC_EN") (class "Default")
      (node (ref "U7") (pin "15") (pinfunction "P1.3/ADC3_15") (pintype "passive"))
      (node (ref "U9") (pin "6") (pinfunction "E#_6") (pintype "passive"))
    )
    (net (code "3") (name "/D_N") (class "Default")
      (node (ref "U8") (pin "2") (pinfunction "UD-_2") (pintype "passive"))
    )
    (net (code "4") (name "/D_P") (class "Default")
      (node (ref "U8") (pin "1") (pinfunction "UD+_1") (pintype "passive"))
    )
    (net (code "5") (name "/MCU_RXD") (class "Default")
      (node (ref "D15") (pin "2") (pinfunction "A_2") (pintype "passive"))
      (node (ref "P2") (pin "2") (pinfunction "2_2") (pintype "passive"))
      (node (ref "U7") (pin "2") (pinfunction "RXD/P3.0_2") (pintype "passive"))
    )
    (net (code "6") (name "/MCU_TXD") (class "Default")
      (node (ref "D14") (pin "1") (pinfunction "K_1") (pintype "passive"))
      (node (ref "P2") (pin "3") (pinfunction "3_3") (pintype "passive"))
      (node (ref "U7") (pin "3") (pinfunction "TXD/P3.1_3") (pintype "passive"))
    )
    (net (code "7") (name "/Motor_L+") (class "Default")
      (node (ref "R58") (pin "1") (pinfunction "1_1") (pintype "passive"))
      (node (ref "R72") (pin "2") (pinfunction "2_2") (pintype "passive"))
      (node (ref "U7") (pin "8") (pinfunction "CLKOUT0/ECI/T0/P3.4_8") (pintype "passive"))
    )
    (net (code "8") (name "/Motor_L-") (class "Default")
      (node (ref "R59") (pin "2") (pinfunction "2_2") (pintype "passive"))
      (node (ref "R70") (pin "2") (pinfunction "2_2") (pintype "passive"))
      (node (ref "U7") (pin "12") (pinfunction "P1.0/ADC0_12") (pintype "passive"))
    )
    (net (code "9") (name "/Motor_R+") (class "Default")
      (node (ref "R60") (pin "1") (pinfunction "1_1") (pintype "passive"))
      (node (ref "R73") (pin "2") (pinfunction "2_2") (pintype "passive"))
      (node (ref "U7") (pin "9") (pinfunction "CLKOUT1/CCP1/T1/P3.5_9") (pintype "passive"))
    )
    (net (code "10") (name "/Motor_R-") (class "Default")
      (node (ref "R61") (pin "2") (pinfunction "2_2") (pintype "passive"))
      (node (ref "R71") (pin "2") (pinfunction "2_2") (pintype "passive"))
      (node (ref "U7") (pin "13") (pinfunction "P1.1/ADC1_13") (pintype "passive"))
    )
    (net (code "11") (name "/P3_7") (class "Default")
      (node (ref "LED11") (pin "2") (pinfunction "K_2") (pintype "passive"))
      (node (ref "U7") (pin "11") (pinfunction "P3.7/CCP0_11") (pintype "passive"))
    )
    (net (code "12") (name "/REL_V") (class "Default")
      (node (ref "U7") (pin "19") (pinfunction "P1.7/ADC7_19") (pintype "passive"))
    )
    (net (code "13") (name "/RST") (class "Default")
      (node (ref "R78") (pin "2") (pinfunction "2_2") (pintype "passive"))
      (node (ref "U7") (pin "1") (pinfunction "RST_1") (pintype "passive"))
    )
    (net (code "14") (name "/Red_light_L") (class "Default")
      (node (ref "R56") (pin "1") (pinfunction "1_1") (pintype "passive"))
      (node (ref "TP5") (pin "1") (pinfunction "1_1") (pintype "passive"))
      (node (ref "U7") (pin "6") (pinfunction "INT0#/P3.2_6") (pintype "passive"))
    )
    (net (code "15") (name "/Red_light_R") (class "Default")
      (node (ref "R57") (pin "1") (pinfunction "1_1") (pintype "passive"))
      (node (ref "TP6") (pin "1") (pinfunction "1_1") (pintype "passive"))
      (node (ref "U7") (pin "7") (pinfunction "INT1#/P3.3_7") (pintype "passive"))
    )
    (net (code "16") (name "/S0") (class "Default")
      (node (ref "U7") (pin "16") (pinfunction "P1.4/ADC4_16") (pintype "passive"))
      (node (ref "U9") (pin "11") (pinfunction "S0_11") (pintype "passive"))
    )
    (net (code "17") (name "/S1") (class "Default")
      (node (ref "U7") (pin "17") (pinfunction "P1.5/ADC5_17") (pintype "passive"))
      (node (ref "U9") (pin "10") (pinfunction "S1_10") (pintype "passive"))
    )
    (net (code "18") (name "/S2") (class "Default")
      (node (ref "U7") (pin "18") (pinfunction "P1.6/ADC6_18") (pintype "passive"))
      (node (ref "U9") (pin "9") (pinfunction "S2_9") (pintype "passive"))
    )
    (net (code "19") (name "/Signal_1") (class "Default")
      (node (ref "U9") (pin "13") (pinfunction "Y0_13") (pintype "passive"))
    )
    (net (code "20") (name "/Signal_2") (class "Default")
      (node (ref "U9") (pin "14") (pinfunction "Y1_14") (pintype "passive"))
    )
    (net (code "21") (name "/Signal_3") (class "Default")
      (node (ref "U9") (pin "15") (pinfunction "Y2_15") (pintype "passive"))
    )
    (net (code "22") (name "/Signal_4") (class "Default")
      (node (ref "U9") (pin "12") (pinfunction "Y3_12") (pintype "passive"))
    )
    (net (code "23") (name "/X1") (class "Default")
      (node (ref "C70") (pin "2") (pinfunction "2_2") (pintype "passive"))
      (node (ref "R80") (pin "1") (pinfunction "1_1") (pintype "passive"))
      (node (ref "U7") (pin "5") (pinfunction "XTAL1_5") (pintype "passive"))
      (node (ref "X1") (pin "1") (pinfunction "OSC1_1") (pintype "passive"))
    )
    (net (code "24") (name "/X2") (class "Default")
      (node (ref "C71") (pin "2") (pinfunction "2_2") (pintype "passive"))
      (node (ref "R80") (pin "2") (pinfunction "2_2") (pintype "passive"))
      (node (ref "U7") (pin "4") (pinfunction "XTAL2_4") (pintype "passive"))
      (node (ref "X1") (pin "2") (pinfunction "OSC2_2") (pintype "passive"))
    )
    (net (code "25") (name "3.3V") (class "Default")
      (node (ref "C58") (pin "2") (pinfunction "2_2") (pintype "passive"))
      (node (ref "C59") (pin "2") (pinfunction "2_2") (pintype "passive"))
      (node (ref "C60") (pin "2") (pinfunction "2_2") (pintype "passive"))
      (node (ref "R46") (pin "1") (pinfunction "1_1") (pintype "passive"))
      (node (ref "R46") (pin "2") (pinfunction "2_2") (pintype "passive"))
      (node (ref "R47") (pin "2") (pinfunction "2_2") (pintype "passive"))
      (node (ref "R48") (pin "1") (pinfunction "1_1") (pintype "passive"))
      (node (ref "R48") (pin "2") (pinfunction "2_2") (pintype "passive"))
      (node (ref "R49") (pin "2") (pinfunction "2_2") (pintype "passive"))
      (node (ref "R54") (pin "2") (pinfunction "2_2") (pintype "passive"))
      (node (ref "R55") (pin "2") (pinfunction "2_2") (pintype "passive"))
      (node (ref "R62") (pin "1") (pinfunction "1_1") (pintype "passive"))
      (node (ref "R64") (pin "1") (pinfunction "1_1") (pintype "passive"))
      (node (ref "U6") (pin "8") (pinfunction "VCC+_8") (pintype "power_in"))
    )
    (net (code "26") (name "5V") (class "Default")
      (node (ref "C64") (pin "2") (pinfunction "2_2") (pintype "passive"))
      (node (ref "C65") (pin "2") (pinfunction "2_2") (pintype "passive"))
      (node (ref "C66") (pin "2") (pinfunction "2_2") (pintype "passive"))
      (node (ref "C67") (pin "2") (pinfunction "2_2") (pintype "passive"))
      (node (ref "P1") (pin "1") (pinfunction "1_1") (pintype "passive"))
      (node (ref "P2") (pin "1") (pinfunction "1_1") (pintype "passive"))
      (node (ref "R81") (pin "1") (pinfunction "1_1") (pintype "passive"))
      (node (ref "S1") (pin "2") (pinfunction "2_2") (pintype "passive"))
      (node (ref "U7") (pin "20") (pinfunction "VCC_20") (pintype "passive"))
    )
    (net (code "27") (name "GND") (class "Default")
      (node (ref "C52") (pin "2") (pinfunction "2_2") (pintype "passive"))
      (node (ref "C53") (pin "1") (pinfunction "1_1") (pintype "passive"))
      (node (ref "C54") (pin "1") (pinfunction "1_1") (pintype "passive"))
      (node (ref "C55") (pin "2") (pinfunction "2_2") (pintype "passive"))
      (node (ref "C56") (pin "1") (pinfunction "1_1") (pintype "passive"))
      (node (ref "C57") (pin "1") (pinfunction "1_1") (pintype "passive"))
      (node (ref "C58") (pin "1") (pinfunction "1_1") (pintype "passive"))
      (node (ref "C63") (pin "2") (pinfunction "2_2") (pintype "passive"))
      (node (ref "C64") (pin "1") (pinfunction "1_1") (pintype "passive"))
      (node (ref "C65") (pin "1") (pinfunction "1_1") (pintype "passive"))
      (node (ref "C66") (pin "1") (pinfunction "1_1") (pintype "passive"))
      (node (ref "C68") (pin "2") (pinfunction "2_2") (pintype "passive"))
      (node (ref "C69") (pin "2") (pinfunction "2_2") (pintype "passive"))
      (node (ref "C70") (pin "1") (pinfunction "1_1") (pintype "passive"))
      (node (ref "C71") (pin "1") (pinfunction "1_1") (pintype "passive"))
      (node (ref "C72") (pin "2") (pinfunction "2_2") (pintype "passive"))
      (node (ref "C73") (pin "2") (pinfunction "2_2") (pintype "passive"))
      (node (ref "D10") (pin "1") (pinfunction "K_1") (pintype "passive"))
      (node (ref "D11") (pin "1") (pinfunction "K_1") (pintype "passive"))
      (node (ref "D12") (pin "1") (pinfunction "K_1") (pintype "passive"))
      (node (ref "D13") (pin "1") (pinfunction "K_1") (pintype "passive"))
      (node (ref "LED10") (pin "2") (pinfunction "K_2") (pintype "passive"))
      (node (ref "LED7") (pin "1") (pinfunction "A_1") (pintype "passive"))
      (node (ref "LED8") (pin "1") (pinfunction "A_1") (pintype "passive"))
      (node (ref "LED9") (pin "2") (pinfunction "K_2") (pintype "passive"))
      (node (ref "P2") (pin "4") (pinfunction "4_4") (pintype "passive"))
      (node (ref "Q10") (pin "2") (pinfunction "E_2") (pintype "passive"))
      (node (ref "Q11") (pin "2") (pinfunction "E_2") (pintype "passive"))
      (node (ref "Q12") (pin "2") (pinfunction "E_2") (pintype "passive"))
      (node (ref "Q13") (pin "2") (pinfunction "E_2") (pintype "passive"))
      (node (ref "Q14") (pin "2") (pinfunction "E_2") (pintype "passive"))
      (node (ref "Q15") (pin "2") (pinfunction "E_2") (pintype "passive"))
      (node (ref "Q16") (pin "2") (pinfunction "E_2") (pintype "passive"))
      (node (ref "Q9") (pin "2") (pinfunction "E_2") (pintype "passive"))
      (node (ref "R63") (pin "1") (pinfunction "1_1") (pintype "passive"))
      (node (ref "R65") (pin "1") (pinfunction "1_1") (pintype "passive"))
      (node (ref "R74") (pin "1") (pinfunction "1_1") (pintype "passive"))
      (node (ref "R75") (pin "1") (pinfunction "1_1") (pintype "passive"))
      (node (ref "R76") (pin "1") (pinfunction "1_1") (pintype "passive"))
      (node (ref "R77") (pin "1") (pinfunction "1_1") (pintype "passive"))
      (node (ref "R79") (pin "1") (pinfunction "1_1") (pintype "passive"))
      (node (ref "R82") (pin "1") (pinfunction "1_1") (pintype "passive"))
      (node (ref "S1") (pin "3") (pinfunction "3_3") (pintype "passive"))
      (node (ref "S1") (pin "4") (pinfunction "4_4") (pintype "passive"))
      (node (ref "U6") (pin "4") (pinfunction "GND_4") (pintype "power_in"))
      (node (ref "U7") (pin "10") (pinfunction "GND_10") (pintype "passive"))
      (node (ref "U8") (pin "3") (pinfunction "GND_3") (pintype "passive"))
      (node (ref "U9") (pin "8") (pinfunction "GND_8") (pintype "passive"))
    )
    (net (code "28") (name "Motor_5V") (class "Default")
      (node (ref "C52") (pin "1") (pinfunction "1_1") (pintype "passive"))
      (node (ref "C53") (pin "2") (pinfunction "2_2") (pintype "passive"))
      (node (ref "C54") (pin "2") (pinfunction "2_2") (pintype "passive"))
      (node (ref "C55") (pin "1") (pinfunction "1_1") (pintype "passive"))
      (node (ref "C56") (pin "2") (pinfunction "2_2") (pintype "passive"))
      (node (ref "C57") (pin "2") (pinfunction "2_2") (pintype "passive"))
      (node (ref "D5") (pin "2") (pinfunction "A_2") (pintype "passive"))
      (node (ref "D6") (pin "2") (pinfunction "A_2") (pintype "passive"))
      (node (ref "D7") (pin "2") (pinfunction "A_2") (pintype "passive"))
      (node (ref "D8") (pin "2") (pinfunction "A_2") (pintype "passive"))
      (node (ref "D9") (pin "2") (pinfunction "A_2") (pintype "passive"))
      (node (ref "Q5") (pin "2") (pinfunction "E_2") (pintype "passive"))
      (node (ref "Q6") (pin "2") (pinfunction "E_2") (pintype "passive"))
      (node (ref "Q7") (pin "2") (pinfunction "E_2") (pintype "passive"))
      (node (ref "Q8") (pin "2") (pinfunction "E_2") (pintype "passive"))
      (node (ref "R50") (pin "2") (pinfunction "2_2") (pintype "passive"))
      (node (ref "R51") (pin "2") (pinfunction "2_2") (pintype "passive"))
      (node (ref "R52") (pin "2") (pinfunction "2_2") (pintype "passive"))
      (node (ref "R53") (pin "2") (pinfunction "2_2") (pintype "passive"))
      (node (ref "R66") (pin "2") (pinfunction "2_2") (pintype "passive"))
      (node (ref "R67") (pin "2") (pinfunction "2_2") (pintype "passive"))
      (node (ref "R68") (pin "2") (pinfunction "2_2") (pintype "passive"))
      (node (ref "R69") (pin "2") (pinfunction "2_2") (pintype "passive"))
    )
    (net (code "29") (name "Net-(C67-Pad1)") (class "Default")
      (node (ref "C67") (pin "1") (pinfunction "1_1") (pintype "passive"))
      (node (ref "R78") (pin "1") (pinfunction "1_1") (pintype "passive"))
      (node (ref "R79") (pin "2") (pinfunction "2_2") (pintype "passive"))
      (node (ref "S1") (pin "1") (pinfunction "1_1") (pintype "passive"))
    )
    (net (code "30") (name "Net-(D5-K)") (class "Default")
      (node (ref "D5") (pin "1") (pinfunction "K_1") (pintype "passive"))
      (node (ref "P1") (pin "2") (pinfunction "2_2") (pintype "passive"))
    )
    (net (code "31") (name "Net-(D10-A)") (class "Default")
      (node (ref "C61") (pin "1") (pinfunction "1_1") (pintype "passive"))
      (node (ref "D10") (pin "2") (pinfunction "A_2") (pintype "passive"))
      (node (ref "D6") (pin "1") (pinfunction "K_1") (pintype "passive"))
      (node (ref "J3") (pin "1") (pinfunction "1_1") (pintype "passive"))
      (node (ref "Q11") (pin "3") (pinfunction "C_3") (pintype "passive"))
      (node (ref "Q7") (pin "3") (pinfunction "C_3") (pintype "passive"))
    )
    (net (code "32") (name "Net-(D11-A)") (class "Default")
      (node (ref "C61") (pin "2") (pinfunction "2_2") (pintype "passive"))
      (node (ref "D11") (pin "2") (pinfunction "A_2") (pintype "passive"))
      (node (ref "D7") (pin "1") (pinfunction "K_1") (pintype "passive"))
      (node (ref "J3") (pin "2") (pinfunction "2_2") (pintype "passive"))
      (node (ref "Q5") (pin "3") (pinfunction "C_3") (pintype "passive"))
      (node (ref "Q9") (pin "3") (pinfunction "C_3") (pintype "passive"))
    )
    (net (code "33") (name "Net-(D12-A)") (class "Default")
      (node (ref "C62") (pin "1") (pinfunction "1_1") (pintype "passive"))
      (node (ref "D12") (pin "2") (pinfunction "A_2") (pintype "passive"))
      (node (ref "D8") (pin "1") (pinfunction "K_1") (pintype "passive"))
      (node (ref "J4") (pin "1") (pinfunction "1_1") (pintype "passive"))
      (node (ref "Q12") (pin "3") (pinfunction "C_3") (pintype "passive"))
      (node (ref "Q8") (pin "3") (pinfunction "C_3") (pintype "passive"))
    )
    (net (code "34") (name "Net-(D13-A)") (class "Default")
      (node (ref "C62") (pin "2") (pinfunction "2_2") (pintype "passive"))
      (node (ref "D13") (pin "2") (pinfunction "A_2") (pintype "passive"))
      (node (ref "D9") (pin "1") (pinfunction "K_1") (pintype "passive"))
      (node (ref "J4") (pin "2") (pinfunction "2_2") (pintype "passive"))
      (node (ref "Q10") (pin "3") (pinfunction "C_3") (pintype "passive"))
      (node (ref "Q6") (pin "3") (pinfunction "C_3") (pintype "passive"))
    )
    (net (code "35") (name "Net-(D14-A)") (class "Default")
      (node (ref "D14") (pin "2") (pinfunction "A_2") (pintype "passive"))
      (node (ref "U8") (pin "7") (pinfunction "RXD_7") (pintype "passive"))
    )
    (net (code "36") (name "Net-(D15-K)") (class "Default")
      (node (ref "D15") (pin "1") (pinfunction "K_1") (pintype "passive"))
      (node (ref "U8") (pin "6") (pinfunction "TXD_6") (pintype "passive"))
    )
    (net (code "37") (name "Net-(LED7-K)") (class "Default")
      (node (ref "C59") (pin "1") (pinfunction "1_1") (pintype "passive"))
      (node (ref "LED7") (pin "2") (pinfunction "K_2") (pintype "passive"))
      (node (ref "R46") (pin "3") (pinfunction "3_3") (pintype "passive"))
      (node (ref "R47") (pin "1") (pinfunction "1_1") (pintype "passive"))
      (node (ref "U6") (pin "3") (pinfunction "1IN+_3") (pintype "tri_state"))
    )
    (net (code "38") (name "Net-(LED8-K)") (class "Default")
      (node (ref "C60") (pin "1") (pinfunction "1_1") (pintype "passive"))
      (node (ref "LED8") (pin "2") (pinfunction "K_2") (pintype "passive"))
      (node (ref "R48") (pin "3") (pinfunction "3_3") (pintype "passive"))
      (node (ref "R49") (pin "1") (pinfunction "1_1") (pintype "passive"))
      (node (ref "U6") (pin "5") (pinfunction "1IN+_5") (pintype "tri_state"))
    )
    (net (code "39") (name "Net-(LED9-A)") (class "Default")
      (node (ref "LED9") (pin "1") (pinfunction "A_1") (pintype "passive"))
      (node (ref "R54") (pin "1") (pinfunction "1_1") (pintype "passive"))
    )
    (net (code "40") (name "Net-(LED10-A)") (class "Default")
      (node (ref "LED10") (pin "1") (pinfunction "A_1") (pintype "passive"))
      (node (ref "R55") (pin "1") (pinfunction "1_1") (pintype "passive"))
    )
    (net (code "41") (name "Net-(LED11-A)") (class "Default")
      (node (ref "LED11") (pin "1") (pinfunction "A_1") (pintype "passive"))
      (node (ref "R81") (pin "2") (pinfunction "2_2") (pintype "passive"))
    )
    (net (code "42") (name "Net-(Q5-B)") (class "Default")
      (node (ref "Q5") (pin "1") (pinfunction "B_1") (pintype "passive"))
      (node (ref "R51") (pin "1") (pinfunction "1_1") (pintype "passive"))
      (node (ref "R59") (pin "1") (pinfunction "1_1") (pintype "passive"))
    )
    (net (code "43") (name "Net-(Q6-B)") (class "Default")
      (node (ref "Q6") (pin "1") (pinfunction "B_1") (pintype "passive"))
      (node (ref "R53") (pin "1") (pinfunction "1_1") (pintype "passive"))
      (node (ref "R61") (pin "1") (pinfunction "1_1") (pintype "passive"))
    )
    (net (code "44") (name "Net-(Q7-B)") (class "Default")
      (node (ref "Q7") (pin "1") (pinfunction "B_1") (pintype "passive"))
      (node (ref "R50") (pin "1") (pinfunction "1_1") (pintype "passive"))
      (node (ref "R58") (pin "2") (pinfunction "2_2") (pintype "passive"))
    )
    (net (code "45") (name "Net-(Q8-B)") (class "Default")
      (node (ref "Q8") (pin "1") (pinfunction "B_1") (pintype "passive"))
      (node (ref "R52") (pin "1") (pinfunction "1_1") (pintype "passive"))
      (node (ref "R60") (pin "2") (pinfunction "2_2") (pintype "passive"))
    )
    (net (code "46") (name "Net-(Q10-B)") (class "Default")
      (node (ref "Q10") (pin "1") (pinfunction "B_1") (pintype "passive"))
      (node (ref "Q14") (pin "3") (pinfunction "C_3") (pintype "passive"))
      (node (ref "R69") (pin "1") (pinfunction "1_1") (pintype "passive"))
    )
    (net (code "47") (name "Net-(Q11-B)") (class "Default")
      (node (ref "Q11") (pin "1") (pinfunction "B_1") (pintype "passive"))
      (node (ref "Q15") (pin "3") (pinfunction "C_3") (pintype "passive"))
      (node (ref "R66") (pin "1") (pinfunction "1_1") (pintype "passive"))
    )
    (net (code "48") (name "Net-(Q12-B)") (class "Default")
      (node (ref "Q12") (pin "1") (pinfunction "B_1") (pintype "passive"))
      (node (ref "Q16") (pin "3") (pinfunction "C_3") (pintype "passive"))
      (node (ref "R68") (pin "1") (pinfunction "1_1") (pintype "passive"))
    )
    (net (code "49") (name "Net-(Q13-B)") (class "Default")
      (node (ref "Q13") (pin "1") (pinfunction "B_1") (pintype "passive"))
      (node (ref "R72") (pin "1") (pinfunction "1_1") (pintype "passive"))
      (node (ref "R76") (pin "2") (pinfunction "2_2") (pintype "passive"))
    )
    (net (code "50") (name "Net-(Q13-C)") (class "Default")
      (node (ref "Q13") (pin "3") (pinfunction "C_3") (pintype "passive"))
      (node (ref "Q9") (pin "1") (pinfunction "B_1") (pintype "passive"))
      (node (ref "R67") (pin "1") (pinfunction "1_1") (pintype "passive"))
    )
    (net (code "51") (name "Net-(Q14-B)") (class "Default")
      (node (ref "Q14") (pin "1") (pinfunction "B_1") (pintype "passive"))
      (node (ref "R73") (pin "1") (pinfunction "1_1") (pintype "passive"))
      (node (ref "R77") (pin "2") (pinfunction "2_2") (pintype "passive"))
    )
    (net (code "52") (name "Net-(Q15-B)") (class "Default")
      (node (ref "Q15") (pin "1") (pinfunction "B_1") (pintype "passive"))
      (node (ref "R70") (pin "1") (pinfunction "1_1") (pintype "passive"))
      (node (ref "R74") (pin "2") (pinfunction "2_2") (pintype "passive"))
    )
    (net (code "53") (name "Net-(Q16-B)") (class "Default")
      (node (ref "Q16") (pin "1") (pinfunction "B_1") (pintype "passive"))
      (node (ref "R71") (pin "1") (pinfunction "1_1") (pintype "passive"))
      (node (ref "R75") (pin "2") (pinfunction "2_2") (pintype "passive"))
    )
    (net (code "54") (name "Net-(U6A-1IN-)") (class "Default")
      (node (ref "R62") (pin "2") (pinfunction "2_2") (pintype "passive"))
      (node (ref "R63") (pin "2") (pinfunction "2_2") (pintype "passive"))
      (node (ref "U6") (pin "2") (pinfunction "1IN-_2") (pintype "tri_state"))
    )
    (net (code "55") (name "Net-(U6A-OUT)") (class "Default")
      (node (ref "R56") (pin "2") (pinfunction "2_2") (pintype "passive"))
      (node (ref "U6") (pin "1") (pinfunction "OUT_1") (pintype "output"))
    )
    (net (code "56") (name "Net-(U6B-1IN-)") (class "Default")
      (node (ref "R64") (pin "2") (pinfunction "2_2") (pintype "passive"))
      (node (ref "R65") (pin "2") (pinfunction "2_2") (pintype "passive"))
      (node (ref "U6") (pin "6") (pinfunction "1IN-_6") (pintype "tri_state"))
    )
    (net (code "57") (name "Net-(U6B-OUT)") (class "Default")
      (node (ref "R57") (pin "2") (pinfunction "2_2") (pintype "passive"))
      (node (ref "U6") (pin "7") (pinfunction "OUT_7") (pintype "output"))
    )
    (net (code "58") (name "Net-(U8-V3)") (class "Default")
      (node (ref "C63") (pin "1") (pinfunction "1_1") (pintype "passive"))
      (node (ref "U8") (pin "8") (pinfunction "V3_8") (pintype "passive"))
    )
    (net (code "59") (name "Net-(U9-VEE)") (class "Default")
      (node (ref "R82") (pin "2") (pinfunction "2_2") (pintype "passive"))
      (node (ref "U9") (pin "7") (pinfunction "VEE_7") (pintype "passive"))
    )
    (net (code "60") (name "VBUS") (class "Default")
      (node (ref "C68") (pin "1") (pinfunction "1_1") (pintype "passive"))
      (node (ref "C69") (pin "1") (pinfunction "1_1") (pintype "passive"))
      (node (ref "U8") (pin "5") (pinfunction "VCC_5") (pintype "passive"))
    )
    (net (code "61") (name "VCC") (class "Default")
      (node (ref "C72") (pin "1") (pinfunction "1_1") (pintype "passive"))
      (node (ref "C73") (pin "1") (pinfunction "1_1") (pintype "passive"))
      (node (ref "U9") (pin "16") (pinfunction "VCC_16") (pintype "passive"))
    )
    (net (code "62") (name "unconnected-(U8-RTS#-Pad4)") (class "Default")
      (node (ref "U8") (pin "4") (pinfunction "RTS#_4") (pintype "passive+no_connect"))
    )
    (net (code "63") (name "unconnected-(U9-Y4-Pad1)") (class "Default")
      (node (ref "U9") (pin "1") (pinfunction "Y4_1") (pintype "passive+no_connect"))
    )
    (net (code "64") (name "unconnected-(U9-Y5-Pad5)") (class "Default")
      (node (ref "U9") (pin "5") (pinfunction "Y5_5") (pintype "passive+no_connect"))
    )
    (net (code "65") (name "unconnected-(U9-Y6-Pad2)") (class "Default")
      (node (ref "U9") (pin "2") (pinfunction "Y6_2") (pintype "passive+no_connect"))
    )
    (net (code "66") (name "unconnected-(U9-Y7-Pad4)") (class "Default")
      (node (ref "U9") (pin "4") (pinfunction "Y7_4") (pintype "passive+no_connect"))
    )
  )
)
